# Suprise.net
KiCad netlist of a schematic drawn in Altium Designer
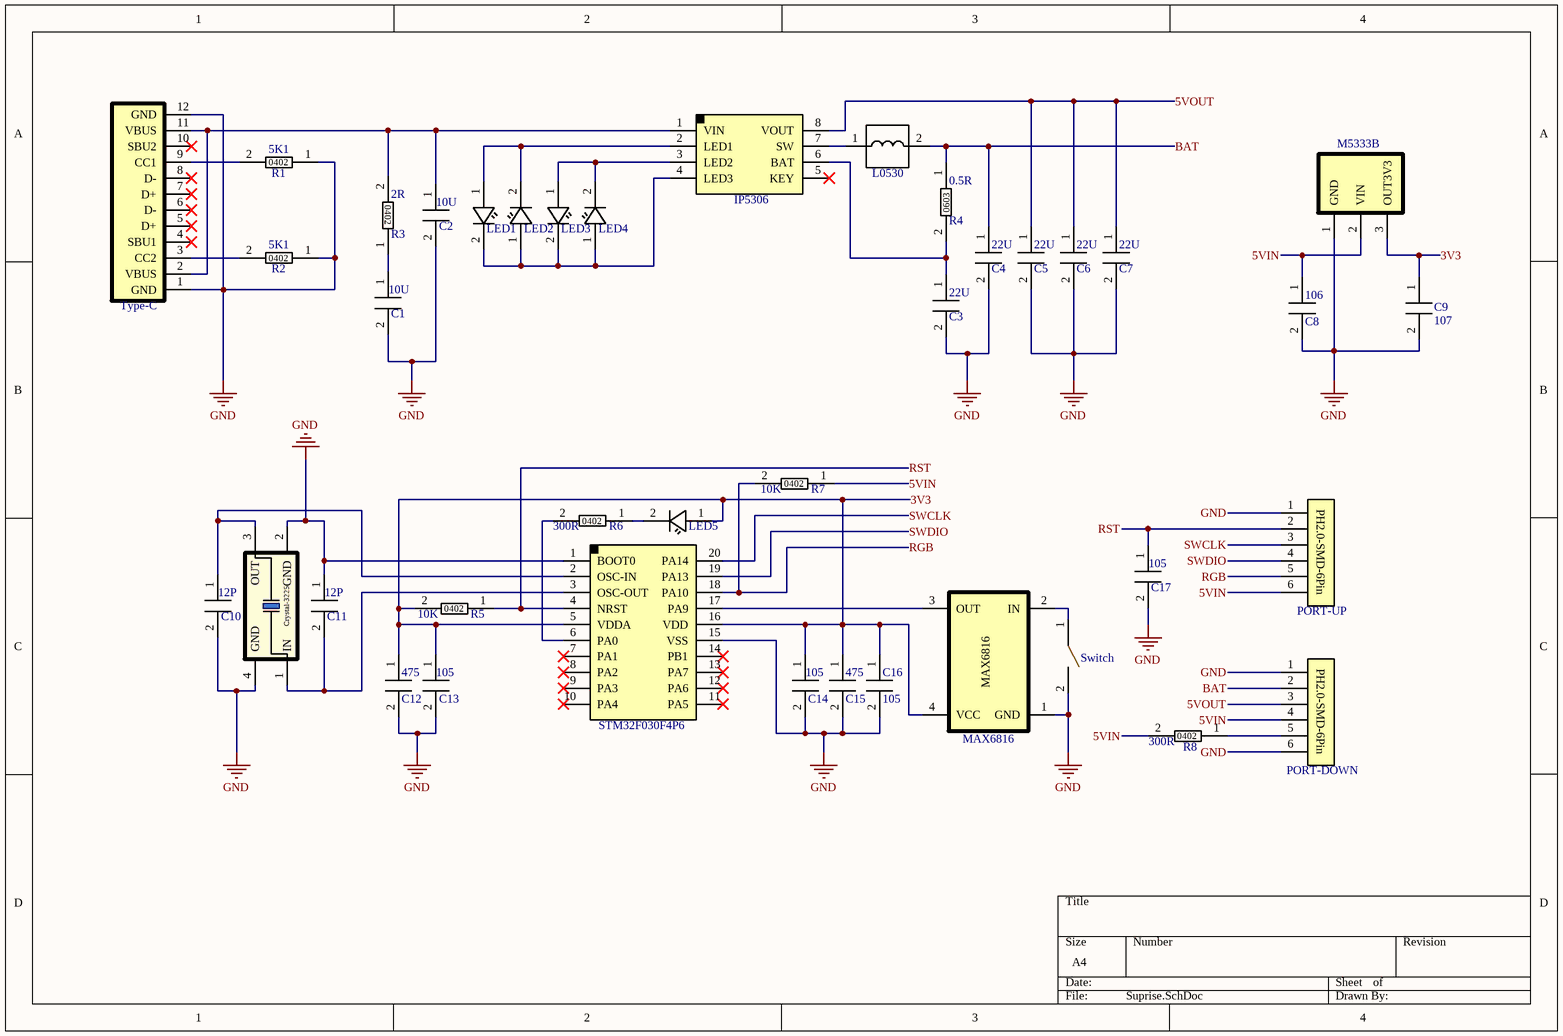
[diagram p0: Suprise.SchDoc]

(export (version "E")
  (design (tool "Eeschema 10.0.6"))
  (components
    (comp (ref "3225-8MHz")
      (value "Crystal-3225")
      (footprint "Crystal-3225")
      (libsource (lib "Crystal-3225") (part "Crystal-3225"))
    )
    (comp (ref "C1") (value "10U") (footprint "CAP0402") (libsource (lib "CAP0402") (part "CAP0402")))
    (comp (ref "C2") (value "10U") (footprint "CAP0402") (libsource (lib "CAP0402") (part "CAP0402")))
    (comp (ref "C3") (value "22U") (footprint "CAP0402") (libsource (lib "CAP0402") (part "CAP0402")))
    (comp (ref "C4") (value "22U") (footprint "CAP0402") (libsource (lib "CAP0402") (part "CAP0402")))
    (comp (ref "C5") (value "22U") (footprint "CAP0402") (libsource (lib "CAP0402") (part "CAP0402")))
    (comp (ref "C6") (value "22U") (footprint "CAP0402") (libsource (lib "CAP0402") (part "CAP0402")))
    (comp (ref "C7") (value "22U") (footprint "CAP0402") (libsource (lib "CAP0402") (part "CAP0402")))
    (comp (ref "C8") (value "106") (footprint "CAP0402") (libsource (lib "CAP0402") (part "CAP0402")))
    (comp (ref "C9") (value "107") (footprint "CAP0402") (libsource (lib "CAP0402") (part "CAP0402")))
    (comp (ref "C10") (value "12P") (footprint "CAP0402") (libsource (lib "CAP0402") (part "CAP0402")))
    (comp (ref "C11") (value "12P") (footprint "CAP0402") (libsource (lib "CAP0402") (part "CAP0402")))
    (comp (ref "C12") (value "475") (footprint "CAP0402") (libsource (lib "CAP0402") (part "CAP0402")))
    (comp (ref "C13") (value "105") (footprint "CAP0402") (libsource (lib "CAP0402") (part "CAP0402")))
    (comp (ref "C14") (value "105") (footprint "CAP0402") (libsource (lib "CAP0402") (part "CAP0402")))
    (comp (ref "C15") (value "475") (footprint "CAP0402") (libsource (lib "CAP0402") (part "CAP0402")))
    (comp (ref "C16") (value "105") (footprint "CAP0402") (libsource (lib "CAP0402") (part "CAP0402")))
    (comp (ref "C17") (value "105") (footprint "CAP0402") (libsource (lib "CAP0402") (part "CAP0402")))
    (comp (ref "IP5306") (value "IP5306") (footprint "IP5306") (libsource (lib "IP5306") (part "IP5306")))
    (comp (ref "L0530") (value "IND0530") (footprint "IND0530") (libsource (lib "IND0530") (part "IND0530")))
    (comp (ref "LED1") (value "LED0603") (footprint "LED0603") (libsource (lib "LED0603") (part "LED0603")))
    (comp (ref "LED2") (value "LED0603") (footprint "LED0603") (libsource (lib "LED0603") (part "LED0603")))
    (comp (ref "LED3") (value "LED0603") (footprint "LED0603") (libsource (lib "LED0603") (part "LED0603")))
    (comp (ref "LED4") (value "LED0603") (footprint "LED0603") (libsource (lib "LED0603") (part "LED0603")))
    (comp (ref "LED5") (value "LED0603") (footprint "LED0603") (libsource (lib "LED0603") (part "LED0603")))
    (comp (ref "M5333B") (value "M5333B") (footprint "M5333B") (libsource (lib "M5333B") (part "M5333B")))
    (comp (ref "MAX6816")
      (value "MAX6816")
      (footprint "MAX6816")
      (libsource (lib "MAX6816") (part "MAX6816"))
    )
    (comp (ref "PORT-DOWN")
      (value "PH2.0-SMD-6Pin")
      (footprint "PH2.0-SMD-6Pin")
      (libsource (lib "PH2.0-SMD-6Pin") (part "PH2.0-SMD-6Pin"))
    )
    (comp (ref "PORT-UP")
      (value "PH2.0-SMD-6Pin")
      (footprint "PH2.0-SMD-6Pin")
      (libsource (lib "PH2.0-SMD-6Pin") (part "PH2.0-SMD-6Pin"))
    )
    (comp (ref "R1") (value "5K1") (footprint "RES0402") (libsource (lib "RES0402") (part "RES0402")))
    (comp (ref "R2") (value "5K1") (footprint "RES0402") (libsource (lib "RES0402") (part "RES0402")))
    (comp (ref "R3") (value "2R") (footprint "RES0402") (libsource (lib "") (part "RES0402_1")))
    (comp (ref "R4") (value "0.5R") (footprint "RES0603") (libsource (lib "RES0603") (part "RES0603")))
    (comp (ref "R5") (value "10K") (footprint "RES0402") (libsource (lib "RES0402") (part "RES0402")))
    (comp (ref "R6") (value "300R") (footprint "RES0402") (libsource (lib "RES0402") (part "RES0402")))
    (comp (ref "R7") (value "10K") (footprint "RES0402") (libsource (lib "RES0402") (part "RES0402")))
    (comp (ref "R8") (value "300R") (footprint "RES0402") (libsource (lib "RES0402") (part "RES0402")))
    (comp (ref "STM32F030F4P6")
      (value "STM32F030F4P6")
      (footprint "STM32F030F4P6")
      (libsource (lib "STM32F030F4P6") (part "STM32F030F4P6"))
    )
    (comp (ref "Switch")
      (value "Key-4*4*1.5")
      (footprint "Key-4*4*1.5")
      (libsource (lib "Key4415") (part "Key-4*4*1.5"))
    )
    (comp (ref "Type-C")
      (value "Type-C-IN-16Pin")
      (footprint "SinkBoard-Type-C-IN-16Pin")
      (libsource (lib "Type-C-IN-16Pin") (part "Type-C-IN-16Pin"))
    )
  )
  (nets
    (net (code "1") (name "/3V3") (class "Default")
      (node (ref "C12") (pin "1") (pinfunction "1_1") (pintype "passive"))
      (node (ref "C13") (pin "1") (pinfunction "1_1") (pintype "passive"))
      (node (ref "C14") (pin "1") (pinfunction "1_1") (pintype "passive"))
      (node (ref "C15") (pin "1") (pinfunction "1_1") (pintype "passive"))
      (node (ref "C16") (pin "1") (pinfunction "1_1") (pintype "passive"))
      (node (ref "C9") (pin "1") (pinfunction "1_1") (pintype "passive"))
      (node (ref "LED5") (pin "1") (pinfunction "2_1") (pintype "passive"))
      (node (ref "M5333B") (pin "3") (pinfunction "OUT3V3_3") (pintype "passive"))
      (node (ref "MAX6816") (pin "4") (pinfunction "VCC_4") (pintype "passive"))
      (node (ref "R5") (pin "2") (pinfunction "2_2") (pintype "passive"))
      (node (ref "STM32F030F4P6") (pin "16") (pinfunction "VDD_16") (pintype "passive"))
      (node (ref "STM32F030F4P6") (pin "5") (pinfunction "VDDA_5") (pintype "passive"))
    )
    (net (code "2") (name "/5VIN") (class "Default")
      (node (ref "C8") (pin "1") (pinfunction "1_1") (pintype "passive"))
      (node (ref "M5333B") (pin "2") (pinfunction "VIN_2") (pintype "passive"))
      (node (ref "PORT-DOWN") (pin "4") (pinfunction "4_4") (pintype "passive"))
      (node (ref "PORT-UP") (pin "6") (pinfunction "6_6") (pintype "passive"))
      (node (ref "R7") (pin "1") (pinfunction "1_1") (pintype "passive"))
      (node (ref "R8") (pin "2") (pinfunction "2_2") (pintype "passive"))
    )
    (net (code "3") (name "/5VOUT") (class "Default")
      (node (ref "C5") (pin "1") (pinfunction "1_1") (pintype "passive"))
      (node (ref "C6") (pin "1") (pinfunction "1_1") (pintype "passive"))
      (node (ref "C7") (pin "1") (pinfunction "1_1") (pintype "passive"))
      (node (ref "IP5306") (pin "8") (pinfunction "VOUT_8") (pintype "passive"))
      (node (ref "PORT-DOWN") (pin "3") (pinfunction "3_3") (pintype "passive"))
    )
    (net (code "4") (name "/BAT") (class "Default")
      (node (ref "C4") (pin "1") (pinfunction "1_1") (pintype "passive"))
      (node (ref "L0530") (pin "2") (pinfunction "2_2") (pintype "passive"))
      (node (ref "PORT-DOWN") (pin "2") (pinfunction "2_2") (pintype "passive"))
      (node (ref "R4") (pin "1") (pinfunction "1_1") (pintype "passive"))
    )
    (net (code "5") (name "/RGB") (class "Default")
      (node (ref "PORT-UP") (pin "5") (pinfunction "5_5") (pintype "passive"))
      (node (ref "R7") (pin "2") (pinfunction "2_2") (pintype "passive"))
      (node (ref "STM32F030F4P6") (pin "18") (pinfunction "PA10_18") (pintype "passive"))
    )
    (net (code "6") (name "/RST") (class "Default")
      (node (ref "C17") (pin "1") (pinfunction "1_1") (pintype "passive"))
      (node (ref "PORT-UP") (pin "2") (pinfunction "2_2") (pintype "passive"))
      (node (ref "R5") (pin "1") (pinfunction "1_1") (pintype "passive"))
      (node (ref "STM32F030F4P6") (pin "4") (pinfunction "NRST_4") (pintype "passive"))
    )
    (net (code "7") (name "/SWCLK") (class "Default")
      (node (ref "PORT-UP") (pin "3") (pinfunction "3_3") (pintype "passive"))
      (node (ref "STM32F030F4P6") (pin "20") (pinfunction "PA14_20") (pintype "passive"))
    )
    (net (code "8") (name "/SWDIO") (class "Default")
      (node (ref "PORT-UP") (pin "4") (pinfunction "4_4") (pintype "passive"))
      (node (ref "STM32F030F4P6") (pin "19") (pinfunction "PA13_19") (pintype "passive"))
    )
    (net (code "9") (name "GND") (class "Default")
      (node (ref "3225-8MHz") (pin "2") (pinfunction "GND_2") (pintype "passive"))
      (node (ref "3225-8MHz") (pin "4") (pinfunction "GND_4") (pintype "passive"))
      (node (ref "C1") (pin "2") (pinfunction "2_2") (pintype "passive"))
      (node (ref "C10") (pin "2") (pinfunction "2_2") (pintype "passive"))
      (node (ref "C11") (pin "1") (pinfunction "1_1") (pintype "passive"))
      (node (ref "C12") (pin "2") (pinfunction "2_2") (pintype "passive"))
      (node (ref "C13") (pin "2") (pinfunction "2_2") (pintype "passive"))
      (node (ref "C14") (pin "2") (pinfunction "2_2") (pintype "passive"))
      (node (ref "C15") (pin "2") (pinfunction "2_2") (pintype "passive"))
      (node (ref "C16") (pin "2") (pinfunction "2_2") (pintype "passive"))
      (node (ref "C17") (pin "2") (pinfunction "2_2") (pintype "passive"))
      (node (ref "C2") (pin "2") (pinfunction "2_2") (pintype "passive"))
      (node (ref "C3") (pin "2") (pinfunction "2_2") (pintype "passive"))
      (node (ref "C4") (pin "2") (pinfunction "2_2") (pintype "passive"))
      (node (ref "C5") (pin "2") (pinfunction "2_2") (pintype "passive"))
      (node (ref "C6") (pin "2") (pinfunction "2_2") (pintype "passive"))
      (node (ref "C7") (pin "2") (pinfunction "2_2") (pintype "passive"))
      (node (ref "C8") (pin "2") (pinfunction "2_2") (pintype "passive"))
      (node (ref "C9") (pin "2") (pinfunction "2_2") (pintype "passive"))
      (node (ref "M5333B") (pin "1") (pinfunction "GND_1") (pintype "passive"))
      (node (ref "MAX6816") (pin "1") (pinfunction "GND_1") (pintype "passive"))
      (node (ref "PORT-DOWN") (pin "1") (pinfunction "1_1") (pintype "passive"))
      (node (ref "PORT-DOWN") (pin "6") (pinfunction "6_6") (pintype "passive"))
      (node (ref "PORT-UP") (pin "1") (pinfunction "1_1") (pintype "passive"))
      (node (ref "R1") (pin "1") (pinfunction "1_1") (pintype "passive"))
      (node (ref "R2") (pin "1") (pinfunction "1_1") (pintype "passive"))
      (node (ref "STM32F030F4P6") (pin "1") (pinfunction "BOOT0_1") (pintype "passive"))
      (node (ref "STM32F030F4P6") (pin "15") (pinfunction "VSS_15") (pintype "passive"))
      (node (ref "Switch") (pin "2") (pinfunction "2_2") (pintype "passive"))
      (node (ref "Type-C") (pin "1") (pinfunction "GND_1") (pintype "passive"))
      (node (ref "Type-C") (pin "12") (pinfunction "GND_12") (pintype "passive"))
    )
    (net (code "10") (name "Net-(3225-8MHz-IN)") (class "Default")
      (node (ref "3225-8MHz") (pin "1") (pinfunction "IN_1") (pintype "passive"))
      (node (ref "C11") (pin "2") (pinfunction "2_2") (pintype "passive"))
      (node (ref "STM32F030F4P6") (pin "3") (pinfunction "OSC-OUT_3") (pintype "passive"))
    )
    (net (code "11") (name "Net-(3225-8MHz-OUT)") (class "Default")
      (node (ref "3225-8MHz") (pin "3") (pinfunction "OUT_3") (pintype "passive"))
      (node (ref "C10") (pin "1") (pinfunction "1_1") (pintype "passive"))
      (node (ref "STM32F030F4P6") (pin "2") (pinfunction "OSC-IN_2") (pintype "passive"))
    )
    (net (code "12") (name "Net-(C1-Pad1)") (class "Default")
      (node (ref "C1") (pin "1") (pinfunction "1_1") (pintype "passive"))
      (node (ref "R3") (pin "1") (pinfunction "1_1") (pintype "passive"))
    )
    (net (code "13") (name "Net-(IP5306-BAT)") (class "Default")
      (node (ref "C3") (pin "1") (pinfunction "1_1") (pintype "passive"))
      (node (ref "IP5306") (pin "6") (pinfunction "BAT_6") (pintype "passive"))
      (node (ref "R4") (pin "2") (pinfunction "2_2") (pintype "passive"))
    )
    (net (code "14") (name "Net-(IP5306-LED1)") (class "Default")
      (node (ref "IP5306") (pin "2") (pinfunction "LED1_2") (pintype "passive"))
      (node (ref "LED1") (pin "1") (pinfunction "2_1") (pintype "passive"))
      (node (ref "LED2") (pin "2") (pinfunction "2_2") (pintype "passive"))
    )
    (net (code "15") (name "Net-(IP5306-LED2)") (class "Default")
      (node (ref "IP5306") (pin "3") (pinfunction "LED2_3") (pintype "passive"))
      (node (ref "LED3") (pin "1") (pinfunction "2_1") (pintype "passive"))
      (node (ref "LED4") (pin "2") (pinfunction "2_2") (pintype "passive"))
    )
    (net (code "16") (name "Net-(IP5306-LED3)") (class "Default")
      (node (ref "IP5306") (pin "4") (pinfunction "LED3_4") (pintype "passive"))
      (node (ref "LED1") (pin "2") (pinfunction "2_2") (pintype "passive"))
      (node (ref "LED2") (pin "1") (pinfunction "2_1") (pintype "passive"))
      (node (ref "LED3") (pin "2") (pinfunction "2_2") (pintype "passive"))
      (node (ref "LED4") (pin "1") (pinfunction "2_1") (pintype "passive"))
    )
    (net (code "17") (name "Net-(IP5306-SW)") (class "Default")
      (node (ref "IP5306") (pin "7") (pinfunction "SW_7") (pintype "passive"))
      (node (ref "L0530") (pin "1") (pinfunction "1_1") (pintype "passive"))
    )
    (net (code "18") (name "Net-(IP5306-VIN)") (class "Default")
      (node (ref "C2") (pin "1") (pinfunction "1_1") (pintype "passive"))
      (node (ref "IP5306") (pin "1") (pinfunction "VIN_1") (pintype "passive"))
      (node (ref "R3") (pin "2") (pinfunction "2_2") (pintype "passive"))
      (node (ref "Type-C") (pin "11") (pinfunction "VBUS_11") (pintype "passive"))
      (node (ref "Type-C") (pin "2") (pinfunction "VBUS_2") (pintype "passive"))
    )
    (net (code "19") (name "Net-(LED5-Pad2)") (class "Default")
      (node (ref "LED5") (pin "2") (pinfunction "2_2") (pintype "passive"))
      (node (ref "R6") (pin "1") (pinfunction "1_1") (pintype "passive"))
    )
    (net (code "20") (name "Net-(MAX6816-IN)") (class "Default")
      (node (ref "MAX6816") (pin "2") (pinfunction "IN_2") (pintype "passive"))
      (node (ref "Switch") (pin "1") (pinfunction "1_1") (pintype "passive"))
    )
    (net (code "21") (name "Net-(MAX6816-OUT)") (class "Default")
      (node (ref "MAX6816") (pin "3") (pinfunction "OUT_3") (pintype "passive"))
      (node (ref "STM32F030F4P6") (pin "17") (pinfunction "PA9_17") (pintype "passive"))
    )
    (net (code "22") (name "Net-(PORT-DOWN-Pad5)") (class "Default")
      (node (ref "PORT-DOWN") (pin "5") (pinfunction "5_5") (pintype "passive"))
      (node (ref "R8") (pin "1") (pinfunction "1_1") (pintype "passive"))
    )
    (net (code "23") (name "Net-(STM32F030F4P6-PA0)") (class "Default")
      (node (ref "R6") (pin "2") (pinfunction "2_2") (pintype "passive"))
      (node (ref "STM32F030F4P6") (pin "6") (pinfunction "PA0_6") (pintype "passive"))
    )
    (net (code "24") (name "Net-(Type-C-CC1)") (class "Default")
      (node (ref "R1") (pin "2") (pinfunction "2_2") (pintype "passive"))
      (node (ref "Type-C") (pin "9") (pinfunction "CC1_9") (pintype "passive"))
    )
    (net (code "25") (name "Net-(Type-C-CC2)") (class "Default")
      (node (ref "R2") (pin "2") (pinfunction "2_2") (pintype "passive"))
      (node (ref "Type-C") (pin "3") (pinfunction "CC2_3") (pintype "passive"))
    )
    (net (code "26") (name "unconnected-(IP5306-KEY-Pad5)") (class "Default")
      (node (ref "IP5306") (pin "5") (pinfunction "KEY_5") (pintype "passive+no_connect"))
    )
    (net (code "27") (name "unconnected-(STM32F030F4P6-PA1-Pad7)") (class "Default")
      (node (ref "STM32F030F4P6") (pin "7") (pinfunction "PA1_7") (pintype "passive+no_connect"))
    )
    (net (code "28") (name "unconnected-(STM32F030F4P6-PA2-Pad8)") (class "Default")
      (node (ref "STM32F030F4P6") (pin "8") (pinfunction "PA2_8") (pintype "passive+no_connect"))
    )
    (net (code "29") (name "unconnected-(STM32F030F4P6-PA3-Pad9)") (class "Default")
      (node (ref "STM32F030F4P6") (pin "9") (pinfunction "PA3_9") (pintype "passive+no_connect"))
    )
    (net (code "30") (name "unconnected-(STM32F030F4P6-PA4-Pad10)") (class "Default")
      (node (ref "STM32F030F4P6") (pin "10") (pinfunction "PA4_10") (pintype "passive+no_connect"))
    )
    (net (code "31") (name "unconnected-(STM32F030F4P6-PA5-Pad11)") (class "Default")
      (node (ref "STM32F030F4P6") (pin "11") (pinfunction "PA5_11") (pintype "passive+no_connect"))
    )
    (net (code "32") (name "unconnected-(STM32F030F4P6-PA6-Pad12)") (class "Default")
      (node (ref "STM32F030F4P6") (pin "12") (pinfunction "PA6_12") (pintype "passive+no_connect"))
    )
    (net (code "33") (name "unconnected-(STM32F030F4P6-PA7-Pad13)") (class "Default")
      (node (ref "STM32F030F4P6") (pin "13") (pinfunction "PA7_13") (pintype "passive+no_connect"))
    )
    (net (code "34") (name "unconnected-(STM32F030F4P6-PB1-Pad14)") (class "Default")
      (node (ref "STM32F030F4P6") (pin "14") (pinfunction "PB1_14") (pintype "passive+no_connect"))
    )
    (net (code "35") (name "unconnected-(Type-C-D+-Pad5)") (class "Default")
      (node (ref "Type-C") (pin "5") (pinfunction "D+_5") (pintype "passive+no_connect"))
    )
    (net (code "36") (name "unconnected-(Type-C-D+-Pad7)") (class "Default")
      (node (ref "Type-C") (pin "7") (pinfunction "D+_7") (pintype "passive+no_connect"))
    )
    (net (code "37") (name "unconnected-(Type-C-D--Pad6)") (class "Default")
      (node (ref "Type-C") (pin "6") (pinfunction "D-_6") (pintype "passive+no_connect"))
    )
    (net (code "38") (name "unconnected-(Type-C-D--Pad8)") (class "Default")
      (node (ref "Type-C") (pin "8") (pinfunction "D-_8") (pintype "passive+no_connect"))
    )
    (net (code "39") (name "unconnected-(Type-C-SBU1-Pad4)") (class "Default")
      (node (ref "Type-C") (pin "4") (pinfunction "SBU1_4") (pintype "passive+no_connect"))
    )
    (net (code "40") (name "unconnected-(Type-C-SBU2-Pad10)") (class "Default")
      (node (ref "Type-C") (pin "10") (pinfunction "SBU2_10") (pintype "passive+no_connect"))
    )
  )
)
